# KEY4.net
KiCad netlist of a schematic drawn in Altium Designer
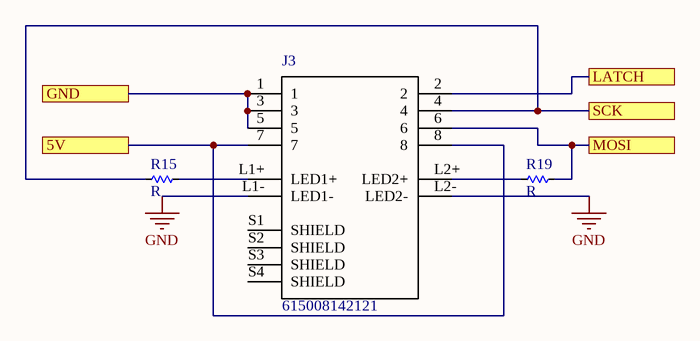
[diagram p0: KEY4.SchDoc]

(export (version "E")
  (design (tool "Eeschema 10.0.6"))
  (components
    (comp (ref "J3")
      (value "615008142121")
      (footprint "RJ45_8P8C")
      (description "Conn, Rj45 Jack, Shld, 1port, 8p8c, Cat5")
      (fields (field (name "MF") "WÃ¼rth Elektronik"))
      (libsource (lib "nhan") (part "RJ45_8P8C"))
    )
    (comp (ref "R15") (value "R") (footprint "RES-SMD-0603_BIG") (libsource (lib "nhan") (part "R")))
    (comp (ref "R19") (value "R") (footprint "RES-SMD-0603_BIG") (libsource (lib "nhan") (part "R")))
  )
  (nets
    (net (code "1") (name "/5V") (class "Default")
      (node (ref "J3") (pin "7") (pinfunction "7_7") (pintype "passive"))
      (node (ref "J3") (pin "8") (pinfunction "8_8") (pintype "passive"))
    )
    (net (code "2") (name "/LATCH") (class "Default")
      (node (ref "J3") (pin "2") (pinfunction "2_2") (pintype "passive"))
    )
    (net (code "3") (name "/MOSI") (class "Default")
      (node (ref "J3") (pin "6") (pinfunction "6_6") (pintype "passive"))
      (node (ref "R19") (pin "1") (pinfunction "1_1") (pintype "passive"))
    )
    (net (code "4") (name "/SCK") (class "Default")
      (node (ref "J3") (pin "4") (pinfunction "4_4") (pintype "passive"))
      (node (ref "R15") (pin "2") (pinfunction "2_2") (pintype "passive"))
    )
    (net (code "5") (name "GND") (class "Default")
      (node (ref "J3") (pin "1") (pinfunction "1_1") (pintype "passive"))
      (node (ref "J3") (pin "3") (pinfunction "3_3") (pintype "passive"))
      (node (ref "J3") (pin "5") (pinfunction "5_5") (pintype "passive"))
      (node (ref "J3") (pin "L1-") (pinfunction "LED1-_L1-") (pintype "passive"))
      (node (ref "J3") (pin "L2-") (pinfunction "LED2-_L2-") (pintype "passive"))
    )
    (net (code "6") (name "Net-(J3-LED1+)") (class "Default")
      (node (ref "J3") (pin "L1+") (pinfunction "LED1+_L1+") (pintype "passive"))
      (node (ref "R15") (pin "1") (pinfunction "1_1") (pintype "passive"))
    )
    (net (code "7") (name "Net-(J3-LED2+)") (class "Default")
      (node (ref "J3") (pin "L2+") (pinfunction "LED2+_L2+") (pintype "passive"))
      (node (ref "R19") (pin "2") (pinfunction "2_2") (pintype "passive"))
    )
    (net (code "8") (name "unconnected-(J3-SHIELD-PadS1)") (class "Default")
      (node (ref "J3") (pin "S1") (pinfunction "SHIELD_S1") (pintype "passive"))
    )
    (net (code "9") (name "unconnected-(J3-SHIELD-PadS2)") (class "Default")
      (node (ref "J3") (pin "S2") (pinfunction "SHIELD_S2") (pintype "passive"))
    )
    (net (code "10") (name "unconnected-(J3-SHIELD-PadS3)") (class "Default")
      (node (ref "J3") (pin "S3") (pinfunction "SHIELD_S3") (pintype "passive"))
    )
    (net (code "11") (name "unconnected-(J3-SHIELD-PadS4)") (class "Default")
      (node (ref "J3") (pin "S4") (pinfunction "SHIELD_S4") (pintype "passive"))
    )
  )
)
